# Dimmer2.net
KiCad netlist of a schematic drawn in EAGLE
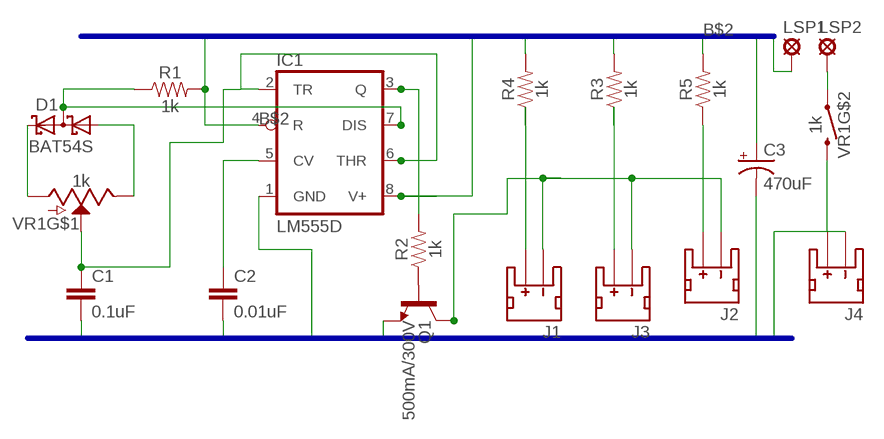
[diagram p0: schematic, sheet 1]

(export (version "E")
  (design (tool "Eeschema 10.0.6"))
  (components
    (comp (ref "C1")
      (value "0.1uF")
      (footprint "eagle-import:C0805")
      (libsource (lib "eagle-import") (part "C"))
    )
    (comp (ref "C2")
      (value "0.01uF")
      (footprint "eagle-import:C0402")
      (libsource (lib "eagle-import") (part "CC0402"))
    )
    (comp (ref "C3")
      (value "470uF")
      (footprint "eagle-import:085CS_1AW")
      (libsource (lib "eagle-import") (part "CPOL-US085CS-1AW"))
    )
    (comp (ref "D1")
      (value "BAT54S")
      (footprint "eagle-import:SOT23")
      (libsource (lib "eagle-import") (part "BAT54S"))
    )
    (comp (ref "IC1")
      (value "LM555D")
      (footprint "eagle-import:SO08")
      (libsource (lib "eagle-import") (part "555DLM"))
    )
    (comp (ref "J1")
      (value "JST_2MM_MALE")
      (footprint "eagle-import:JST-2-SMD")
      (libsource (lib "eagle-import") (part "JST_2MM_MALE"))
    )
    (comp (ref "J2")
      (value "JST_2MM_MALE")
      (footprint "eagle-import:JST-2-SMD")
      (libsource (lib "eagle-import") (part "JST_2MM_MALE"))
    )
    (comp (ref "J3")
      (value "JST_2MM_MALE")
      (footprint "eagle-import:JST-2-SMD")
      (libsource (lib "eagle-import") (part "JST_2MM_MALE"))
    )
    (comp (ref "J4")
      (value "JST_2MM_MALE")
      (footprint "eagle-import:JST-2-SMD")
      (libsource (lib "eagle-import") (part "JST_2MM_MALE"))
    )
    (comp (ref "LSP1")
      (value "LSP10")
      (footprint "eagle-import:LSP10")
      (libsource (lib "eagle-import") (part "LSP10"))
    )
    (comp (ref "LSP2")
      (value "LSP10")
      (footprint "eagle-import:LSP10")
      (libsource (lib "eagle-import") (part "LSP10"))
    )
    (comp (ref "Q1")
      (value "500mA/300V")
      (footprint "eagle-import:SOT23-3")
      (libsource (lib "eagle-import") (part "TRANS_NPN-MMBTA42"))
    )
    (comp (ref "R1")
      (value "1k")
      (footprint "eagle-import:0603")
      (libsource (lib "eagle-import") (part "1KOHM-0603-1/10W-1%"))
    )
    (comp (ref "R2")
      (value "1k")
      (footprint "eagle-import:0603")
      (libsource (lib "eagle-import") (part "1KOHM-0603-1/10W-1%"))
    )
    (comp (ref "R3")
      (value "1k")
      (footprint "eagle-import:0603")
      (libsource (lib "eagle-import") (part "1KOHM-0603-1/10W-1%"))
    )
    (comp (ref "R4")
      (value "1k")
      (footprint "eagle-import:0603")
      (libsource (lib "eagle-import") (part "1KOHM-0603-1/10W-1%"))
    )
    (comp (ref "R5")
      (value "1k")
      (footprint "eagle-import:0603")
      (libsource (lib "eagle-import") (part "1KOHM-0603-1/10W-1%"))
    )
    (comp (ref "VR1")
      (value "1k")
      (footprint "eagle-import:POT-SWITCH-PTH")
      (libsource (lib "eagle-import") (part "POTENTIOMETER_W/SWITCHPOT_PTH_SWITCH"))
    )
  )
  (nets
    (net (code "1") (name "/B$2") (class "Default")
      (node (ref "C3") (pin "+") (pinfunction "+_+") (pintype "passive"))
      (node (ref "IC1") (pin "4") (pinfunction "R_4") (pintype "input"))
      (node (ref "IC1") (pin "8") (pinfunction "V+_8") (pintype "power_in"))
      (node (ref "LSP1") (pin "MP") (pinfunction "MP_MP") (pintype "passive"))
      (node (ref "R1") (pin "2") (pinfunction "2_2") (pintype "passive"))
      (node (ref "R3") (pin "2") (pinfunction "2_2") (pintype "passive"))
      (node (ref "R4") (pin "2") (pinfunction "2_2") (pintype "passive"))
      (node (ref "R5") (pin "2") (pinfunction "2_2") (pintype "passive"))
    )
    (net (code "2") (name "/GND") (class "Default")
      (node (ref "C1") (pin "2") (pinfunction "2_2") (pintype "passive"))
      (node (ref "C2") (pin "2") (pinfunction "2_2") (pintype "passive"))
      (node (ref "C3") (pin "-") (pinfunction "-_-") (pintype "passive"))
      (node (ref "IC1") (pin "1") (pinfunction "GND_1") (pintype "power_in"))
      (node (ref "J4") (pin "1") (pinfunction "-_1") (pintype "bidirectional"))
      (node (ref "Q1") (pin "2") (pinfunction "E_2") (pintype "passive"))
    )
    (net (code "4") (name "Net-(D1-A1)") (class "Default")
      (node (ref "D1") (pin "1") (pinfunction "A1_1") (pintype "passive"))
      (node (ref "VR1") (pin "3") (pinfunction "E_3") (pintype "passive"))
    )
    (net (code "5") (name "Net-(D1-C1A2)") (class "Default")
      (node (ref "D1") (pin "3") (pinfunction "C1A2_3") (pintype "passive"))
      (node (ref "IC1") (pin "7") (pinfunction "DIS_7") (pintype "input"))
      (node (ref "R1") (pin "1") (pinfunction "1_1") (pintype "passive"))
    )
    (net (code "6") (name "Net-(D1-C2)") (class "Default")
      (node (ref "D1") (pin "2") (pinfunction "C2_2") (pintype "passive"))
      (node (ref "VR1") (pin "1") (pinfunction "A_1") (pintype "passive"))
    )
    (net (code "7") (name "Net-(IC1-CV)") (class "Default")
      (node (ref "C2") (pin "1") (pinfunction "1_1") (pintype "passive"))
      (node (ref "IC1") (pin "5") (pinfunction "CV_5") (pintype "input"))
    )
    (net (code "8") (name "Net-(IC1-Q)") (class "Default")
      (node (ref "IC1") (pin "3") (pinfunction "Q_3") (pintype "output"))
      (node (ref "R2") (pin "2") (pinfunction "2_2") (pintype "passive"))
    )
    (net (code "9") (name "Net-(IC1-THR)") (class "Default")
      (node (ref "C1") (pin "1") (pinfunction "1_1") (pintype "passive"))
      (node (ref "IC1") (pin "2") (pinfunction "TR_2") (pintype "input"))
      (node (ref "IC1") (pin "6") (pinfunction "THR_6") (pintype "input"))
      (node (ref "VR1") (pin "2") (pinfunction "S_2") (pintype "passive"))
    )
    (net (code "10") (name "Net-(J1-+)") (class "Default")
      (node (ref "J1") (pin "2") (pinfunction "+_2") (pintype "bidirectional"))
      (node (ref "R4") (pin "1") (pinfunction "1_1") (pintype "passive"))
    )
    (net (code "11") (name "Net-(J1--)") (class "Default")
      (node (ref "J1") (pin "1") (pinfunction "-_1") (pintype "bidirectional"))
      (node (ref "J2") (pin "1") (pinfunction "-_1") (pintype "bidirectional"))
      (node (ref "J3") (pin "1") (pinfunction "-_1") (pintype "bidirectional"))
      (node (ref "Q1") (pin "3") (pinfunction "C_3") (pintype "passive"))
    )
    (net (code "12") (name "Net-(J2-+)") (class "Default")
      (node (ref "J2") (pin "2") (pinfunction "+_2") (pintype "bidirectional"))
      (node (ref "R5") (pin "1") (pinfunction "1_1") (pintype "passive"))
    )
    (net (code "13") (name "Net-(J3-+)") (class "Default")
      (node (ref "J3") (pin "2") (pinfunction "+_2") (pintype "bidirectional"))
      (node (ref "R3") (pin "1") (pinfunction "1_1") (pintype "passive"))
    )
    (net (code "14") (name "Net-(J4-+)") (class "Default")
      (node (ref "J4") (pin "2") (pinfunction "+_2") (pintype "bidirectional"))
      (node (ref "VR1") (pin "S2") (pinfunction "2_S2") (pintype "passive"))
    )
    (net (code "15") (name "Net-(Q1-B)") (class "Default")
      (node (ref "Q1") (pin "1") (pinfunction "B_1") (pintype "passive"))
      (node (ref "R2") (pin "1") (pinfunction "1_1") (pintype "passive"))
    )
    (net (code "16") (name "Net-(VR1B-1)") (class "Default")
      (node (ref "LSP2") (pin "MP") (pinfunction "MP_MP") (pintype "passive"))
      (node (ref "VR1") (pin "S1") (pinfunction "1_S1") (pintype "passive"))
    )
    (net (code "17") (name "unconnected-(J1-PAD1-PadNC1)") (class "Default")
      (node (ref "J1") (pin "NC1") (pinfunction "PAD1_NC1") (pintype "bidirectional"))
    )
    (net (code "18") (name "unconnected-(J1-PAD2-PadNC2)") (class "Default")
      (node (ref "J1") (pin "NC2") (pinfunction "PAD2_NC2") (pintype "bidirectional"))
    )
    (net (code "19") (name "unconnected-(J2-PAD1-PadNC1)") (class "Default")
      (node (ref "J2") (pin "NC1") (pinfunction "PAD1_NC1") (pintype "bidirectional"))
    )
    (net (code "20") (name "unconnected-(J2-PAD2-PadNC2)") (class "Default")
      (node (ref "J2") (pin "NC2") (pinfunction "PAD2_NC2") (pintype "bidirectional"))
    )
    (net (code "21") (name "unconnected-(J3-PAD1-PadNC1)") (class "Default")
      (node (ref "J3") (pin "NC1") (pinfunction "PAD1_NC1") (pintype "bidirectional"))
    )
    (net (code "22") (name "unconnected-(J3-PAD2-PadNC2)") (class "Default")
      (node (ref "J3") (pin "NC2") (pinfunction "PAD2_NC2") (pintype "bidirectional"))
    )
    (net (code "23") (name "unconnected-(J4-PAD1-PadNC1)") (class "Default")
      (node (ref "J4") (pin "NC1") (pinfunction "PAD1_NC1") (pintype "bidirectional"))
    )
    (net (code "24") (name "unconnected-(J4-PAD2-PadNC2)") (class "Default")
      (node (ref "J4") (pin "NC2") (pinfunction "PAD2_NC2") (pintype "bidirectional"))
    )
  )
)
